# 17_SD_CARD.net
KiCad netlist of a schematic drawn in Altium Designer
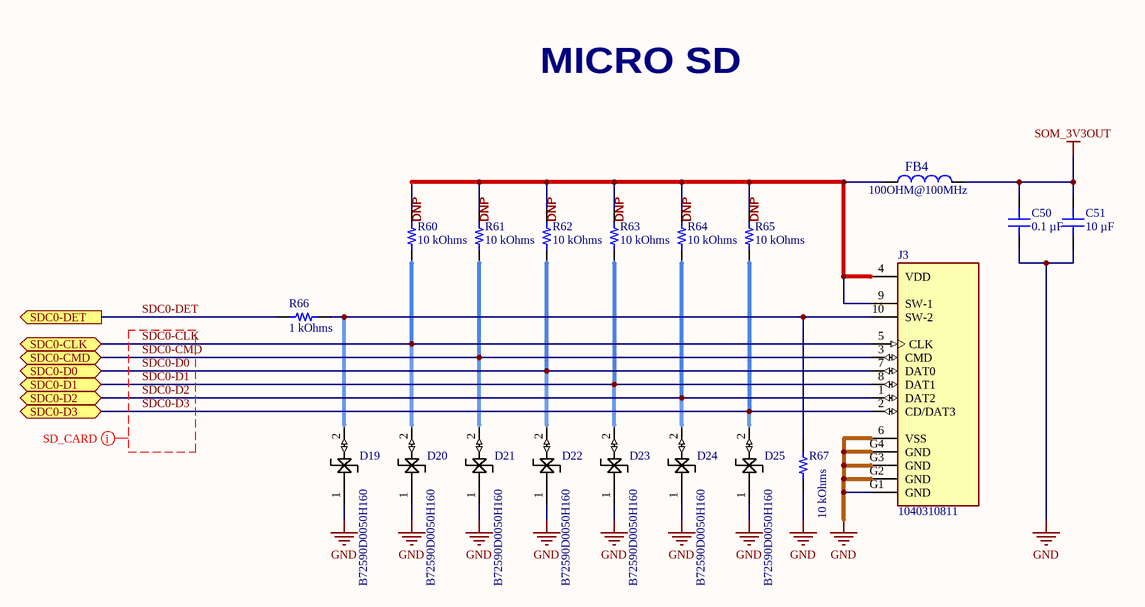
[diagram p0: 17_SD_CARD.SchDoc]

(export (version "E")
  (design (tool "Eeschema 10.0.6"))
  (components
    (comp (ref "C50")
      (value "0.1 µF")
      (footprint "CAP 0603_1608")
      (description "CAP CER 0.1UF 50V X7R 0603")
      (fields
        (field (name "PART NUMBER") "VJ0603Y104KXAPW1BC")
        (field (name "MANUFACTURER") "Vishay Vitramon")
      )
      (libsource (lib "Celestial Altium Library - altium_library") (part "Capacitor"))
    )
    (comp (ref "C51")
      (value "10 µF")
      (footprint "CAP 0603_1608")
      (description "CAP CER 10UF 16V X5R 0603")
      (fields (field (name "PART NUMBER") "KGM15CR51C106KT") (field (name "MANUFACTURER") "KYOCERA AVX"))
      (libsource (lib "Celestial Altium Library - altium_library") (part "Capacitor"))
    )
    (comp (ref "D19")
      (value "B72590D0050H160")
      (footprint "SOD1005X60N")
      (description "VARISTOR 150V 0402")
      (fields (field (name "MANUFACTURER") "TDK EPCOS"))
      (libsource (lib "HW_HOLLAND_NCDM_MONITOR_R1") (part "B72590D0050H160"))
    )
    (comp (ref "D20")
      (value "B72590D0050H160")
      (footprint "SOD1005X60N")
      (description "VARISTOR 150V 0402")
      (fields (field (name "MANUFACTURER") "TDK EPCOS"))
      (libsource (lib "HW_HOLLAND_NCDM_MONITOR_R1") (part "B72590D0050H160"))
    )
    (comp (ref "D21")
      (value "B72590D0050H160")
      (footprint "SOD1005X60N")
      (description "VARISTOR 150V 0402")
      (fields (field (name "MANUFACTURER") "TDK EPCOS"))
      (libsource (lib "HW_HOLLAND_NCDM_MONITOR_R1") (part "B72590D0050H160"))
    )
    (comp (ref "D22")
      (value "B72590D0050H160")
      (footprint "SOD1005X60N")
      (description "VARISTOR 150V 0402")
      (fields (field (name "MANUFACTURER") "TDK EPCOS"))
      (libsource (lib "HW_HOLLAND_NCDM_MONITOR_R1") (part "B72590D0050H160"))
    )
    (comp (ref "D23")
      (value "B72590D0050H160")
      (footprint "SOD1005X60N")
      (description "VARISTOR 150V 0402")
      (fields (field (name "MANUFACTURER") "TDK EPCOS"))
      (libsource (lib "HW_HOLLAND_NCDM_MONITOR_R1") (part "B72590D0050H160"))
    )
    (comp (ref "D24")
      (value "B72590D0050H160")
      (footprint "SOD1005X60N")
      (description "VARISTOR 150V 0402")
      (fields (field (name "MANUFACTURER") "TDK EPCOS"))
      (libsource (lib "HW_HOLLAND_NCDM_MONITOR_R1") (part "B72590D0050H160"))
    )
    (comp (ref "D25")
      (value "B72590D0050H160")
      (footprint "SOD1005X60N")
      (description "VARISTOR 150V 0402")
      (fields (field (name "MANUFACTURER") "TDK EPCOS"))
      (libsource (lib "HW_HOLLAND_NCDM_MONITOR_R1") (part "B72590D0050H160"))
    )
    (comp (ref "FB4")
      (value "100OHM@100MHz")
      (footprint "FB 0603(1608)")
      (description "100 Ohms @ 100 MHz 1 Power Line Ferrite Bead 0603 (1608 Metric) 2A 40mOhm")
      (fields
        (field (name "MANUFACTURER") "TDK")
        (field (name "MANUFACTURER PART NUMBER") "MPZ1608Y101BTA00")
      )
      (libsource (lib "HW_HOLLAND_NCDM_MONITOR_R1") (part "FB0603_100OHM_100MHz"))
    )
    (comp (ref "J3")
      (value "1040310811")
      (footprint "MOLEX_104031-0811")
      (description "1.10mm Pitch microSD Memory Card Connector, SMT, Push-Pull Type, 1.42mm Height, with Detect Switch")
      (fields (field (name "MANUFACTURER") "Molex"))
      (libsource (lib "HW_HOLLAND_NCDM_MONITOR_R1") (part "1040310811"))
    )
    (comp (ref "R60")
      (value "10 kOhms")
      (footprint "RES 0402_1005")
      (description "RES 10K OHM 0.1% 1/10W 0402")
      (fields
        (field (name "PART NUMBER") "RP73PF1E10KBTD")
        (field (name "MANUFACTURER") "TE Connectivity Passive Product")
      )
      (libsource (lib "Celestial Altium Library - altium_library") (part "Resistor"))
    )
    (comp (ref "R61")
      (value "10 kOhms")
      (footprint "RES 0402_1005")
      (description "RES 10K OHM 0.1% 1/10W 0402")
      (fields
        (field (name "PART NUMBER") "RP73PF1E10KBTD")
        (field (name "MANUFACTURER") "TE Connectivity Passive Product")
      )
      (libsource (lib "Celestial Altium Library - altium_library") (part "Resistor"))
    )
    (comp (ref "R62")
      (value "10 kOhms")
      (footprint "RES 0402_1005")
      (description "RES 10K OHM 0.1% 1/10W 0402")
      (fields
        (field (name "PART NUMBER") "RP73PF1E10KBTD")
        (field (name "MANUFACTURER") "TE Connectivity Passive Product")
      )
      (libsource (lib "Celestial Altium Library - altium_library") (part "Resistor"))
    )
    (comp (ref "R63")
      (value "10 kOhms")
      (footprint "RES 0402_1005")
      (description "RES 10K OHM 0.1% 1/10W 0402")
      (fields
        (field (name "PART NUMBER") "RP73PF1E10KBTD")
        (field (name "MANUFACTURER") "TE Connectivity Passive Product")
      )
      (libsource (lib "Celestial Altium Library - altium_library") (part "Resistor"))
    )
    (comp (ref "R64")
      (value "10 kOhms")
      (footprint "RES 0402_1005")
      (description "RES 10K OHM 0.1% 1/10W 0402")
      (fields
        (field (name "PART NUMBER") "RP73PF1E10KBTD")
        (field (name "MANUFACTURER") "TE Connectivity Passive Product")
      )
      (libsource (lib "Celestial Altium Library - altium_library") (part "Resistor"))
    )
    (comp (ref "R65")
      (value "10 kOhms")
      (footprint "RES 0402_1005")
      (description "RES 10K OHM 0.1% 1/10W 0402")
      (fields
        (field (name "PART NUMBER") "RP73PF1E10KBTD")
        (field (name "MANUFACTURER") "TE Connectivity Passive Product")
      )
      (libsource (lib "Celestial Altium Library - altium_library") (part "Resistor"))
    )
    (comp (ref "R66")
      (value "1 kOhms")
      (footprint "RES 0402_1005")
      (description "0402 ANTI-SULFUR RES. , 0.5%, 1K")
      (fields
        (field (name "PART NUMBER") "ERJ-U02D1001X")
        (field (name "MANUFACTURER") "Panasonic Electronic Components")
      )
      (libsource (lib "Celestial Altium Library - altium_library") (part "Resistor"))
    )
    (comp (ref "R67")
      (value "10 kOhms")
      (footprint "RES 0402_1005")
      (description "RES 10K OHM 0.1% 1/10W 0402")
      (fields
        (field (name "PART NUMBER") "RP73PF1E10KBTD")
        (field (name "MANUFACTURER") "TE Connectivity Passive Product")
      )
      (libsource (lib "Celestial Altium Library - altium_library") (part "Resistor"))
    )
  )
  (nets
    (net (code "1") (name "/SDC0-CLK") (class "Default")
      (node (ref "D20") (pin "2") (pinfunction "I/OLINE_2") (pintype "bidirectional"))
      (node (ref "J3") (pin "5") (pinfunction "CLK_5") (pintype "input"))
      (node (ref "R60") (pin "1") (pinfunction "1_1") (pintype "passive"))
    )
    (net (code "2") (name "/SDC0-CMD") (class "Default")
      (node (ref "D21") (pin "2") (pinfunction "I/OLINE_2") (pintype "bidirectional"))
      (node (ref "J3") (pin "3") (pinfunction "CMD_3") (pintype "bidirectional"))
      (node (ref "R61") (pin "1") (pinfunction "1_1") (pintype "passive"))
    )
    (net (code "3") (name "/SDC0-D0") (class "Default")
      (node (ref "D22") (pin "2") (pinfunction "I/OLINE_2") (pintype "bidirectional"))
      (node (ref "J3") (pin "7") (pinfunction "DAT0_7") (pintype "bidirectional"))
      (node (ref "R62") (pin "1") (pinfunction "1_1") (pintype "passive"))
    )
    (net (code "4") (name "/SDC0-D1") (class "Default")
      (node (ref "D23") (pin "2") (pinfunction "I/OLINE_2") (pintype "bidirectional"))
      (node (ref "J3") (pin "8") (pinfunction "DAT1_8") (pintype "bidirectional"))
      (node (ref "R63") (pin "1") (pinfunction "1_1") (pintype "passive"))
    )
    (net (code "5") (name "/SDC0-D2") (class "Default")
      (node (ref "D24") (pin "2") (pinfunction "I/OLINE_2") (pintype "bidirectional"))
      (node (ref "J3") (pin "1") (pinfunction "DAT2_1") (pintype "bidirectional"))
      (node (ref "R64") (pin "1") (pinfunction "1_1") (pintype "passive"))
    )
    (net (code "6") (name "/SDC0-D3") (class "Default")
      (node (ref "D25") (pin "2") (pinfunction "I/OLINE_2") (pintype "bidirectional"))
      (node (ref "J3") (pin "2") (pinfunction "CD/DAT3_2") (pintype "bidirectional"))
      (node (ref "R65") (pin "1") (pinfunction "1_1") (pintype "passive"))
    )
    (net (code "7") (name "/SDC0-DET") (class "Default")
      (node (ref "R66") (pin "1") (pinfunction "1_1") (pintype "passive"))
    )
    (net (code "8") (name "GND") (class "Default")
      (node (ref "C50") (pin "1") (pinfunction "1_1") (pintype "passive"))
      (node (ref "C51") (pin "1") (pinfunction "1_1") (pintype "passive"))
      (node (ref "D19") (pin "1") (pinfunction "GND_1") (pintype "passive"))
      (node (ref "D20") (pin "1") (pinfunction "GND_1") (pintype "passive"))
      (node (ref "D21") (pin "1") (pinfunction "GND_1") (pintype "passive"))
      (node (ref "D22") (pin "1") (pinfunction "GND_1") (pintype "passive"))
      (node (ref "D23") (pin "1") (pinfunction "GND_1") (pintype "passive"))
      (node (ref "D24") (pin "1") (pinfunction "GND_1") (pintype "passive"))
      (node (ref "D25") (pin "1") (pinfunction "GND_1") (pintype "passive"))
      (node (ref "J3") (pin "6") (pinfunction "VSS_6") (pintype "passive"))
      (node (ref "J3") (pin "G1") (pinfunction "GND_G1") (pintype "passive"))
      (node (ref "J3") (pin "G2") (pinfunction "GND_G2") (pintype "passive"))
      (node (ref "J3") (pin "G3") (pinfunction "GND_G3") (pintype "passive"))
      (node (ref "J3") (pin "G4") (pinfunction "GND_G4") (pintype "passive"))
      (node (ref "R67") (pin "1") (pinfunction "1_1") (pintype "passive"))
    )
    (net (code "9") (name "Net-(D19-I{slash}OLINE)") (class "Default")
      (node (ref "D19") (pin "2") (pinfunction "I/OLINE_2") (pintype "bidirectional"))
      (node (ref "J3") (pin "10") (pinfunction "SW-2_10") (pintype "passive"))
      (node (ref "R66") (pin "2") (pinfunction "2_2") (pintype "passive"))
      (node (ref "R67") (pin "2") (pinfunction "2_2") (pintype "passive"))
    )
    (net (code "10") (name "Net-(J3-SW-1)") (class "Default")
      (node (ref "FB4") (pin "2") (pinfunction "2_2") (pintype "passive"))
      (node (ref "J3") (pin "4") (pinfunction "VDD_4") (pintype "power_in"))
      (node (ref "J3") (pin "9") (pinfunction "SW-1_9") (pintype "passive"))
      (node (ref "R60") (pin "2") (pinfunction "2_2") (pintype "passive"))
      (node (ref "R61") (pin "2") (pinfunction "2_2") (pintype "passive"))
      (node (ref "R62") (pin "2") (pinfunction "2_2") (pintype "passive"))
      (node (ref "R63") (pin "2") (pinfunction "2_2") (pintype "passive"))
      (node (ref "R64") (pin "2") (pinfunction "2_2") (pintype "passive"))
      (node (ref "R65") (pin "2") (pinfunction "2_2") (pintype "passive"))
    )
    (net (code "11") (name "SOM_3V3OUT") (class "Default")
      (node (ref "C50") (pin "2") (pinfunction "2_2") (pintype "passive"))
      (node (ref "C51") (pin "2") (pinfunction "2_2") (pintype "passive"))
      (node (ref "FB4") (pin "1") (pinfunction "1_1") (pintype "passive"))
    )
  )
)
